# P-MT3620RDB-1-6_PIO.net
KiCad netlist of a schematic drawn in Altium Designer
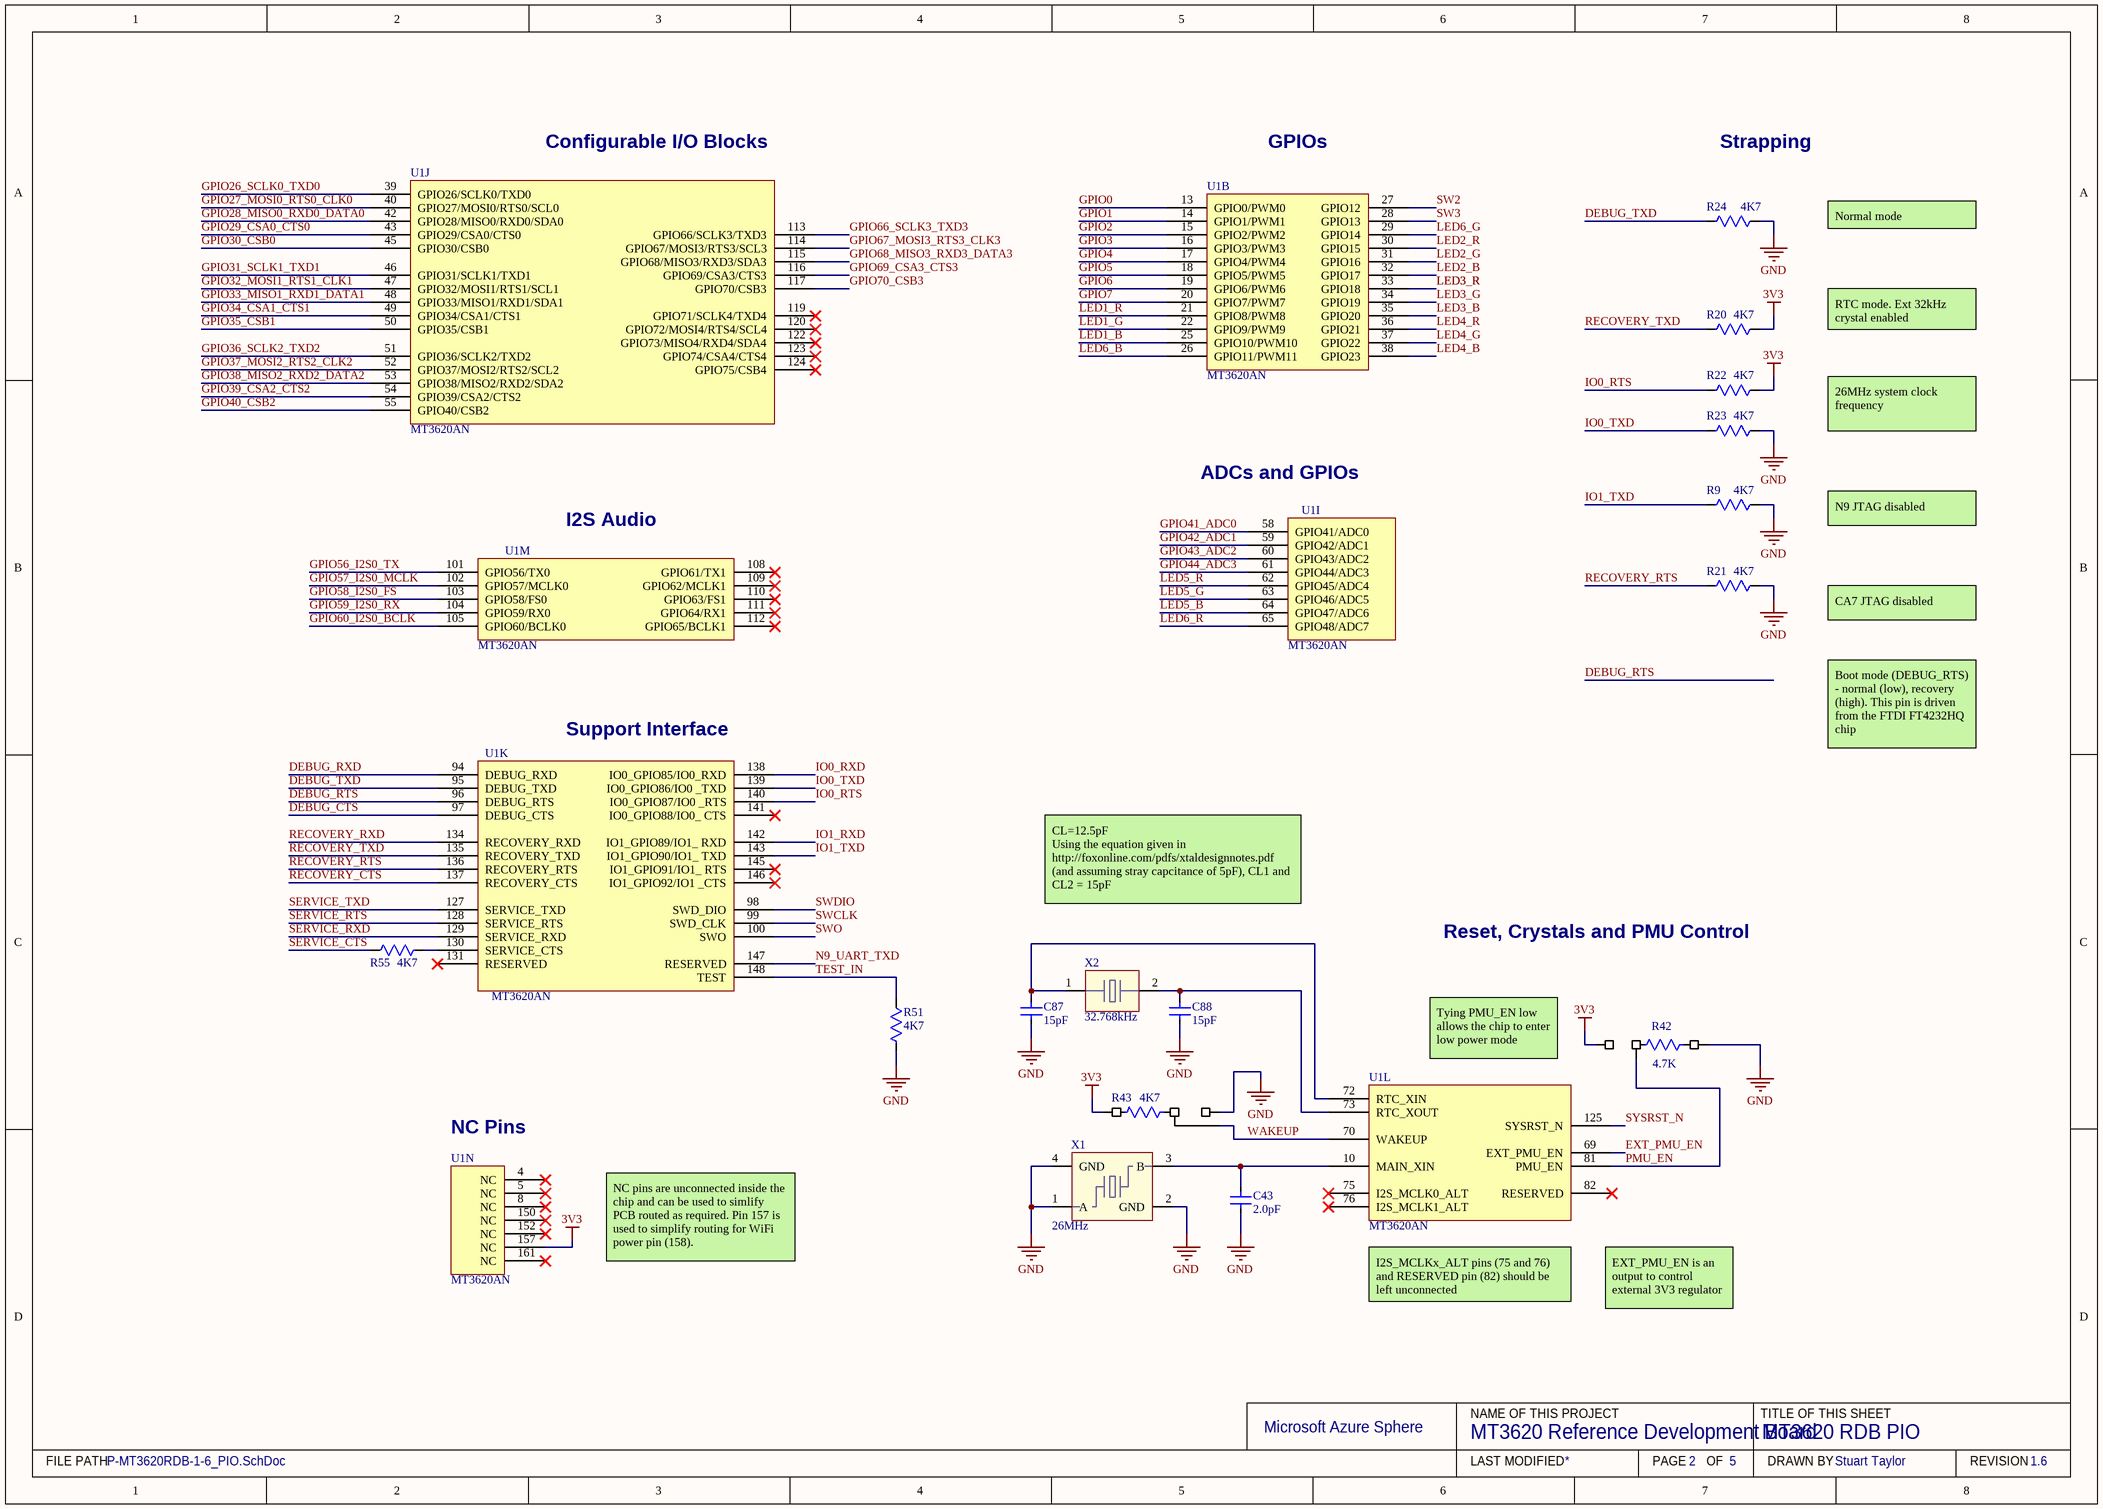
[diagram p0: P-MT3620RDB-1-6_PIO.SchDoc]

(export (version "E")
  (design (tool "Eeschema 10.0.6"))
  (components
    (comp (ref "C43")
      (value "2.0pF")
      (footprint "CAPC1005-EIA0402 0.55MM MED")
      (description "CAP CER 2PF 50V NP0 0402")
      (fields
        (field (name "MANUFACTURER") "TDK Corporation")
        (field (name "MANUFACTURER PART NUMBER") "C1005C0G1H020C050BA")
        (field (name "CAPACITANCE") "2.0pF")
      )
      (libsource (lib "TDK_Capacitor_C_0402") (part "2.0pF 0402 C0G, NP0 50V"))
    )
    (comp (ref "C87")
      (value "15pF")
      (footprint "CAPC1005-EIA0402 0.55MM MED")
      (description "CAP CER 15PF 50V 5% NP0 0402")
      (fields
        (field (name "MANUFACTURER") "TDK Corporation")
        (field (name "MANUFACTURER PART NUMBER") "C1005C0G1H150J050BA")
        (field (name "CAPACITANCE") "15pF")
      )
      (libsource (lib "TDK_Capacitor_C_0402") (part "15pF 0402 C0G, NP0 50V"))
    )
    (comp (ref "C88")
      (value "15pF")
      (footprint "CAPC1005-EIA0402 0.55MM MED")
      (description "CAP CER 15PF 50V 5% NP0 0402")
      (fields
        (field (name "MANUFACTURER") "TDK Corporation")
        (field (name "MANUFACTURER PART NUMBER") "C1005C0G1H150J050BA")
        (field (name "CAPACITANCE") "15pF")
      )
      (libsource (lib "TDK_Capacitor_C_0402") (part "15pF 0402 C0G, NP0 50V"))
    )
    (comp (ref "R9")
      (value "4K7")
      (footprint "RES 0402 MEDIUM DENSITY")
      (description "RES 4.7K OHM 1/10W 1% 0402 SMD")
      (fields
        (field (name "MANUFACTURER") "Panasonic Electronic Components")
        (field (name "MANUFACTURER PART NUMBER") "ERJ-2RKF4701X")
        (field (name "RESISTANCE (OHMS)") "4K7")
      )
      (libsource (lib "Panasonic_Resistor_ERJ2R") (part "4.7K"))
    )
    (comp (ref "R20")
      (value "4K7")
      (footprint "RES 0402 MEDIUM DENSITY")
      (description "RES 4.7K OHM 1/10W 1% 0402 SMD")
      (fields
        (field (name "MANUFACTURER") "Panasonic Electronic Components")
        (field (name "MANUFACTURER PART NUMBER") "ERJ-2RKF4701X")
        (field (name "RESISTANCE (OHMS)") "4K7")
      )
      (libsource (lib "Panasonic_Resistor_ERJ2R") (part "4.7K"))
    )
    (comp (ref "R21")
      (value "4K7")
      (footprint "RES 0402 MEDIUM DENSITY")
      (description "RES 4.7K OHM 1/10W 1% 0402 SMD")
      (fields
        (field (name "MANUFACTURER") "Panasonic Electronic Components")
        (field (name "MANUFACTURER PART NUMBER") "ERJ-2RKF4701X")
        (field (name "RESISTANCE (OHMS)") "4K7")
      )
      (libsource (lib "Panasonic_Resistor_ERJ2R") (part "4.7K"))
    )
    (comp (ref "R22")
      (value "4K7")
      (footprint "RES 0402 MEDIUM DENSITY")
      (description "RES 4.7K OHM 1/10W 1% 0402 SMD")
      (fields
        (field (name "MANUFACTURER") "Panasonic Electronic Components")
        (field (name "MANUFACTURER PART NUMBER") "ERJ-2RKF4701X")
        (field (name "RESISTANCE (OHMS)") "4K7")
      )
      (libsource (lib "Panasonic_Resistor_ERJ2R") (part "4.7K"))
    )
    (comp (ref "R23")
      (value "4K7")
      (footprint "RES 0402 MEDIUM DENSITY")
      (description "RES 4.7K OHM 1/10W 1% 0402 SMD")
      (fields
        (field (name "MANUFACTURER") "Panasonic Electronic Components")
        (field (name "MANUFACTURER PART NUMBER") "ERJ-2RKF4701X")
        (field (name "RESISTANCE (OHMS)") "4K7")
      )
      (libsource (lib "Panasonic_Resistor_ERJ2R") (part "4.7K"))
    )
    (comp (ref "R24")
      (value "4K7")
      (footprint "RES 0402 MEDIUM DENSITY")
      (description "RES 4.7K OHM 1/10W 1% 0402 SMD")
      (fields
        (field (name "MANUFACTURER") "Panasonic Electronic Components")
        (field (name "MANUFACTURER PART NUMBER") "ERJ-2RKF4701X")
        (field (name "RESISTANCE (OHMS)") "4K7")
      )
      (libsource (lib "Panasonic_Resistor_ERJ2R") (part "4.7K"))
    )
    (comp (ref "R42")
      (value "4.7K")
      (footprint "THREE-WAY-0402-NO-SHORT-RIGHT")
      (description "RES SMD 4.7K JUMPER 1/10W 0402")
      (fields
        (field (name "MANUFACTURER") "Panasonic Electronic Components")
        (field (name "MANUFACTURER PART NUMBER") "ERJ-2RKF4701X")
      )
      (libsource (lib "generic-res") (part "THREE-WAY-4K7-0402-NO-SHORT_RIGHT"))
    )
    (comp (ref "R43")
      (value "4K7")
      (footprint "THREE-WAY-0402-NO-SHORT")
      (description "RES SMD 4.7K JUMPER 1/10W 0402")
      (fields
        (field (name "MANUFACTURER") "Panasonic Electronic Components")
        (field (name "MANUFACTURER PART NUMBER") "ERJ-2RKF4701X")
      )
      (libsource (lib "generic-res") (part "THREE-WAY-4K7-0402-NO-SHORT"))
    )
    (comp (ref "R51")
      (value "4K7")
      (footprint "RES 0402 MEDIUM DENSITY")
      (description "RES 4.7K OHM 1/10W 1% 0402 SMD")
      (fields
        (field (name "MANUFACTURER") "Panasonic Electronic Components")
        (field (name "MANUFACTURER PART NUMBER") "ERJ-2RKF4701X")
        (field (name "RESISTANCE (OHMS)") "4K7")
      )
      (libsource (lib "Panasonic_Resistor_ERJ2R") (part "4.7K"))
    )
    (comp (ref "R55")
      (value "4K7")
      (footprint "RES 0402 MEDIUM DENSITY")
      (description "RES 4.7K OHM 1/10W 1% 0402 SMD")
      (fields
        (field (name "MANUFACTURER") "Panasonic Electronic Components")
        (field (name "MANUFACTURER PART NUMBER") "ERJ-2RKF4701X")
        (field (name "RESISTANCE (OHMS)") "4K7")
      )
      (libsource (lib "Panasonic_Resistor_ERJ2R") (part "4.7K"))
    )
    (comp (ref "U1")
      (value "MT3620AN")
      (footprint "MT3620_MaskSquaresVias50")
      (fields (field (name "MANUFACTURER") "MediaTek Inc."))
      (libsource (lib "Microsoft") (part "MT3620AN"))
    )
    (comp (ref "X1")
      (value "26MHz")
      (footprint "CT2520DB26000C0FZZA1")
      (description "26MHz crystal")
      (fields
        (field (name "MANUFACTURER") "Siward")
        (field (name "MANUFACTURER PART NUMBER") "XTL581100-M118-0804")
      )
      (libsource (lib "Siward") (part "XTL581100-M118-0804"))
    )
    (comp (ref "X2")
      (value "32.768kHz")
      (footprint "9HT10-32.768KDZF-T")
      (description "32.768kHz ±20ppm Crystal 12.5pF 70 kOhm -40°C ~ 85°C  Surface Mount 2-SMD")
      (fields
        (field (name "MANUFACTURER") "TXC")
        (field (name "MANUFACTURER PART NUMBER") "9HT10-32.768KDZF-T")
      )
      (libsource (lib "TXC") (part "9HT10-32.768KDZF-T"))
    )
  )
  (nets
    (net (code "1") (name "/DEBUG_CTS") (class "Default")
      (node (ref "U1") (pin "97") (pinfunction "DEBUG_CTS_97") (pintype "passive"))
    )
    (net (code "2") (name "/DEBUG_RTS") (class "Default")
      (node (ref "U1") (pin "96") (pinfunction "DEBUG_RTS_96") (pintype "passive"))
    )
    (net (code "3") (name "/DEBUG_RXD") (class "Default")
      (node (ref "U1") (pin "94") (pinfunction "DEBUG_RXD_94") (pintype "passive"))
    )
    (net (code "4") (name "/DEBUG_TXD") (class "Default")
      (node (ref "R24") (pin "2") (pinfunction "2_2") (pintype "passive"))
      (node (ref "U1") (pin "95") (pinfunction "DEBUG_TXD_95") (pintype "passive"))
    )
    (net (code "5") (name "/EXT_PMU_EN") (class "Default")
      (node (ref "U1") (pin "69") (pinfunction "EXT_PMU_EN_69") (pintype "passive"))
    )
    (net (code "6") (name "/GPIO0") (class "Default")
      (node (ref "U1") (pin "13") (pinfunction "GPIO0/PWM0_13") (pintype "passive"))
    )
    (net (code "7") (name "/GPIO1") (class "Default")
      (node (ref "U1") (pin "14") (pinfunction "GPIO1/PWM1_14") (pintype "passive"))
    )
    (net (code "8") (name "/GPIO2") (class "Default")
      (node (ref "U1") (pin "15") (pinfunction "GPIO2/PWM2_15") (pintype "passive"))
    )
    (net (code "9") (name "/GPIO3") (class "Default")
      (node (ref "U1") (pin "16") (pinfunction "GPIO3/PWM3_16") (pintype "passive"))
    )
    (net (code "10") (name "/GPIO4") (class "Default")
      (node (ref "U1") (pin "17") (pinfunction "GPIO4/PWM4_17") (pintype "passive"))
    )
    (net (code "11") (name "/GPIO5") (class "Default")
      (node (ref "U1") (pin "18") (pinfunction "GPIO5/PWM5_18") (pintype "passive"))
    )
    (net (code "12") (name "/GPIO6") (class "Default")
      (node (ref "U1") (pin "19") (pinfunction "GPIO6/PWM6_19") (pintype "passive"))
    )
    (net (code "13") (name "/GPIO7") (class "Default")
      (node (ref "U1") (pin "20") (pinfunction "GPIO7/PWM7_20") (pintype "passive"))
    )
    (net (code "14") (name "/GPIO26_SCLK0_TXD0") (class "Default")
      (node (ref "U1") (pin "39") (pinfunction "GPIO26/SCLK0/TXD0_39") (pintype "passive"))
    )
    (net (code "15") (name "/GPIO27_MOSI0_RTS0_CLK0") (class "Default")
      (node (ref "U1") (pin "40") (pinfunction "GPIO27/MOSI0/RTS0/SCL0_40") (pintype "passive"))
    )
    (net (code "16") (name "/GPIO28_MISO0_RXD0_DATA0") (class "Default")
      (node (ref "U1") (pin "42") (pinfunction "GPIO28/MISO0/RXD0/SDA0_42") (pintype "passive"))
    )
    (net (code "17") (name "/GPIO29_CSA0_CTS0") (class "Default")
      (node (ref "U1") (pin "43") (pinfunction "GPIO29/CSA0/CTS0_43") (pintype "passive"))
    )
    (net (code "18") (name "/GPIO30_CSB0") (class "Default")
      (node (ref "U1") (pin "45") (pinfunction "GPIO30/CSB0_45") (pintype "passive"))
    )
    (net (code "19") (name "/GPIO31_SCLK1_TXD1") (class "Default")
      (node (ref "U1") (pin "46") (pinfunction "GPIO31/SCLK1/TXD1_46") (pintype "passive"))
    )
    (net (code "20") (name "/GPIO32_MOSI1_RTS1_CLK1") (class "Default")
      (node (ref "U1") (pin "47") (pinfunction "GPIO32/MOSI1/RTS1/SCL1_47") (pintype "passive"))
    )
    (net (code "21") (name "/GPIO33_MISO1_RXD1_DATA1") (class "Default")
      (node (ref "U1") (pin "48") (pinfunction "GPIO33/MISO1/RXD1/SDA1_48") (pintype "passive"))
    )
    (net (code "22") (name "/GPIO34_CSA1_CTS1") (class "Default")
      (node (ref "U1") (pin "49") (pinfunction "GPIO34/CSA1/CTS1_49") (pintype "passive"))
    )
    (net (code "23") (name "/GPIO35_CSB1") (class "Default")
      (node (ref "U1") (pin "50") (pinfunction "GPIO35/CSB1_50") (pintype "passive"))
    )
    (net (code "24") (name "/GPIO36_SCLK2_TXD2") (class "Default")
      (node (ref "U1") (pin "51") (pinfunction "GPIO36/SCLK2/TXD2_51") (pintype "passive"))
    )
    (net (code "25") (name "/GPIO37_MOSI2_RTS2_CLK2") (class "Default")
      (node (ref "U1") (pin "52") (pinfunction "GPIO37/MOSI2/RTS2/SCL2_52") (pintype "passive"))
    )
    (net (code "26") (name "/GPIO38_MISO2_RXD2_DATA2") (class "Default")
      (node (ref "U1") (pin "53") (pinfunction "GPIO38/MISO2/RXD2/SDA2_53") (pintype "passive"))
    )
    (net (code "27") (name "/GPIO39_CSA2_CTS2") (class "Default")
      (node (ref "U1") (pin "54") (pinfunction "GPIO39/CSA2/CTS2_54") (pintype "passive"))
    )
    (net (code "28") (name "/GPIO40_CSB2") (class "Default")
      (node (ref "U1") (pin "55") (pinfunction "GPIO40/CSB2_55") (pintype "passive"))
    )
    (net (code "29") (name "/GPIO41_ADC0") (class "Default")
      (node (ref "U1") (pin "58") (pinfunction "GPIO41/ADC0_58") (pintype "passive"))
    )
    (net (code "30") (name "/GPIO42_ADC1") (class "Default")
      (node (ref "U1") (pin "59") (pinfunction "GPIO42/ADC1_59") (pintype "passive"))
    )
    (net (code "31") (name "/GPIO43_ADC2") (class "Default")
      (node (ref "U1") (pin "60") (pinfunction "GPIO43/ADC2_60") (pintype "passive"))
    )
    (net (code "32") (name "/GPIO44_ADC3") (class "Default")
      (node (ref "U1") (pin "61") (pinfunction "GPIO44/ADC3_61") (pintype "passive"))
    )
    (net (code "33") (name "/GPIO56_I2S0_TX") (class "Default")
      (node (ref "U1") (pin "101") (pinfunction "GPIO56/TX0_101") (pintype "passive"))
    )
    (net (code "34") (name "/GPIO57_I2S0_MCLK") (class "Default")
      (node (ref "U1") (pin "102") (pinfunction "GPIO57/MCLK0_102") (pintype "passive"))
    )
    (net (code "35") (name "/GPIO58_I2S0_FS") (class "Default")
      (node (ref "U1") (pin "103") (pinfunction "GPIO58/FS0_103") (pintype "passive"))
    )
    (net (code "36") (name "/GPIO59_I2S0_RX") (class "Default")
      (node (ref "U1") (pin "104") (pinfunction "GPIO59/RX0_104") (pintype "passive"))
    )
    (net (code "37") (name "/GPIO60_I2S0_BCLK") (class "Default")
      (node (ref "U1") (pin "105") (pinfunction "GPIO60/BCLK0_105") (pintype "passive"))
    )
    (net (code "38") (name "/GPIO66_SCLK3_TXD3") (class "Default")
      (node (ref "U1") (pin "113") (pinfunction "GPIO66/SCLK3/TXD3_113") (pintype "passive"))
    )
    (net (code "39") (name "/GPIO67_MOSI3_RTS3_CLK3") (class "Default")
      (node (ref "U1") (pin "114") (pinfunction "GPIO67/MOSI3/RTS3/SCL3_114") (pintype "passive"))
    )
    (net (code "40") (name "/GPIO68_MISO3_RXD3_DATA3") (class "Default")
      (node (ref "U1") (pin "115") (pinfunction "GPIO68/MISO3/RXD3/SDA3_115") (pintype "passive"))
    )
    (net (code "41") (name "/GPIO69_CSA3_CTS3") (class "Default")
      (node (ref "U1") (pin "116") (pinfunction "GPIO69/CSA3/CTS3_116") (pintype "passive"))
    )
    (net (code "42") (name "/GPIO70_CSB3") (class "Default")
      (node (ref "U1") (pin "117") (pinfunction "GPIO70/CSB3_117") (pintype "passive"))
    )
    (net (code "43") (name "/IO0_RTS") (class "Default")
      (node (ref "R22") (pin "2") (pinfunction "2_2") (pintype "passive"))
      (node (ref "U1") (pin "140") (pinfunction "IO0_GPIO87/IO0__RTS_140") (pintype "passive"))
    )
    (net (code "44") (name "/IO0_RXD") (class "Default")
      (node (ref "U1") (pin "138") (pinfunction "IO0_GPIO85/IO0_RXD_138") (pintype "passive"))
    )
    (net (code "45") (name "/IO0_TXD") (class "Default")
      (node (ref "R23") (pin "2") (pinfunction "2_2") (pintype "passive"))
      (node (ref "U1") (pin "139") (pinfunction "IO0_GPIO86/IO0__TXD_139") (pintype "passive"))
    )
    (net (code "46") (name "/IO1_RXD") (class "Default")
      (node (ref "U1") (pin "142") (pinfunction "IO1_GPIO89/IO1__RXD_142") (pintype "passive"))
    )
    (net (code "47") (name "/IO1_TXD") (class "Default")
      (node (ref "R9") (pin "2") (pinfunction "2_2") (pintype "passive"))
      (node (ref "U1") (pin "143") (pinfunction "IO1_GPIO90/IO1__TXD_143") (pintype "passive"))
    )
    (net (code "48") (name "/LED1_B") (class "Default")
      (node (ref "U1") (pin "25") (pinfunction "GPIO10/PWM10_25") (pintype "passive"))
    )
    (net (code "49") (name "/LED1_G") (class "Default")
      (node (ref "U1") (pin "22") (pinfunction "GPIO9/PWM9_22") (pintype "passive"))
    )
    (net (code "50") (name "/LED1_R") (class "Default")
      (node (ref "U1") (pin "21") (pinfunction "GPIO8/PWM8_21") (pintype "passive"))
    )
    (net (code "51") (name "/LED2_B") (class "Default")
      (node (ref "U1") (pin "32") (pinfunction "GPIO17_32") (pintype "passive"))
    )
    (net (code "52") (name "/LED2_G") (class "Default")
      (node (ref "U1") (pin "31") (pinfunction "GPIO16_31") (pintype "passive"))
    )
    (net (code "53") (name "/LED2_R") (class "Default")
      (node (ref "U1") (pin "30") (pinfunction "GPIO15_30") (pintype "passive"))
    )
    (net (code "54") (name "/LED3_B") (class "Default")
      (node (ref "U1") (pin "35") (pinfunction "GPIO20_35") (pintype "passive"))
    )
    (net (code "55") (name "/LED3_G") (class "Default")
      (node (ref "U1") (pin "34") (pinfunction "GPIO19_34") (pintype "passive"))
    )
    (net (code "56") (name "/LED3_R") (class "Default")
      (node (ref "U1") (pin "33") (pinfunction "GPIO18_33") (pintype "passive"))
    )
    (net (code "57") (name "/LED4_B") (class "Default")
      (node (ref "U1") (pin "38") (pinfunction "GPIO23_38") (pintype "passive"))
    )
    (net (code "58") (name "/LED4_G") (class "Default")
      (node (ref "U1") (pin "37") (pinfunction "GPIO22_37") (pintype "passive"))
    )
    (net (code "59") (name "/LED4_R") (class "Default")
      (node (ref "U1") (pin "36") (pinfunction "GPIO21_36") (pintype "passive"))
    )
    (net (code "60") (name "/LED5_B") (class "Default")
      (node (ref "U1") (pin "64") (pinfunction "GPIO47/ADC6_64") (pintype "passive"))
    )
    (net (code "61") (name "/LED5_G") (class "Default")
      (node (ref "U1") (pin "63") (pinfunction "GPIO46/ADC5_63") (pintype "passive"))
    )
    (net (code "62") (name "/LED5_R") (class "Default")
      (node (ref "U1") (pin "62") (pinfunction "GPIO45/ADC4_62") (pintype "passive"))
    )
    (net (code "63") (name "/LED6_B") (class "Default")
      (node (ref "U1") (pin "26") (pinfunction "GPIO11/PWM11_26") (pintype "passive"))
    )
    (net (code "64") (name "/LED6_G") (class "Default")
      (node (ref "U1") (pin "29") (pinfunction "GPIO14_29") (pintype "passive"))
    )
    (net (code "65") (name "/LED6_R") (class "Default")
      (node (ref "U1") (pin "65") (pinfunction "GPIO48/ADC7_65") (pintype "passive"))
    )
    (net (code "66") (name "/N9_UART_TXD") (class "Default")
      (node (ref "U1") (pin "147") (pinfunction "RESERVED_147") (pintype "passive"))
    )
    (net (code "67") (name "/PMU_EN") (class "Default")
      (node (ref "R42") (pin "2") (pinfunction "2_2") (pintype "passive"))
      (node (ref "U1") (pin "81") (pinfunction "PMU_EN_81") (pintype "passive"))
    )
    (net (code "68") (name "/RECOVERY_CTS") (class "Default")
      (node (ref "U1") (pin "137") (pinfunction "RECOVERY_CTS_137") (pintype "passive"))
    )
    (net (code "69") (name "/RECOVERY_RTS") (class "Default")
      (node (ref "R21") (pin "2") (pinfunction "2_2") (pintype "passive"))
      (node (ref "U1") (pin "136") (pinfunction "RECOVERY_RTS_136") (pintype "passive"))
    )
    (net (code "70") (name "/RECOVERY_RXD") (class "Default")
      (node (ref "U1") (pin "134") (pinfunction "RECOVERY_RXD_134") (pintype "passive"))
    )
    (net (code "71") (name "/RECOVERY_TXD") (class "Default")
      (node (ref "R20") (pin "2") (pinfunction "2_2") (pintype "passive"))
      (node (ref "U1") (pin "135") (pinfunction "RECOVERY_TXD_135") (pintype "passive"))
    )
    (net (code "72") (name "/SERVICE_CTS") (class "Default")
      (node (ref "R55") (pin "1") (pinfunction "1_1") (pintype "passive"))
    )
    (net (code "73") (name "/SERVICE_RTS") (class "Default")
      (node (ref "U1") (pin "128") (pinfunction "SERVICE_RTS_128") (pintype "passive"))
    )
    (net (code "74") (name "/SERVICE_RXD") (class "Default")
      (node (ref "U1") (pin "129") (pinfunction "SERVICE_RXD_129") (pintype "passive"))
    )
    (net (code "75") (name "/SERVICE_TXD") (class "Default")
      (node (ref "U1") (pin "127") (pinfunction "SERVICE_TXD_127") (pintype "passive"))
    )
    (net (code "76") (name "/SW2") (class "Default")
      (node (ref "U1") (pin "27") (pinfunction "GPIO12_27") (pintype "passive"))
    )
    (net (code "77") (name "/SW3") (class "Default")
      (node (ref "U1") (pin "28") (pinfunction "GPIO13_28") (pintype "passive"))
    )
    (net (code "78") (name "/SWCLK") (class "Default")
      (node (ref "U1") (pin "99") (pinfunction "SWD_CLK_99") (pintype "passive"))
    )
    (net (code "79") (name "/SWDIO") (class "Default")
      (node (ref "U1") (pin "98") (pinfunction "SWD_DIO_98") (pintype "passive"))
    )
    (net (code "80") (name "/SWO") (class "Default")
      (node (ref "U1") (pin "100") (pinfunction "SWO_100") (pintype "passive"))
    )
    (net (code "81") (name "/SYSRST_N") (class "Default")
      (node (ref "U1") (pin "125") (pinfunction "SYSRST_N_125") (pintype "passive"))
    )
    (net (code "82") (name "/TEST_IN") (class "Default")
      (node (ref "R51") (pin "1") (pinfunction "1_1") (pintype "passive"))
      (node (ref "U1") (pin "148") (pinfunction "TEST_148") (pintype "passive"))
    )
    (net (code "83") (name "/WAKEUP") (class "Default")
      (node (ref "R43") (pin "2") (pinfunction "2_2") (pintype "passive"))
      (node (ref "U1") (pin "70") (pinfunction "WAKEUP_70") (pintype "passive"))
    )
    (net (code "84") (name "3V3") (class "Default")
      (node (ref "R20") (pin "1") (pinfunction "1_1") (pintype "passive"))
      (node (ref "R22") (pin "1") (pinfunction "1_1") (pintype "passive"))
      (node (ref "R42") (pin "1") (pinfunction "1_1") (pintype "passive"))
      (node (ref "R43") (pin "1") (pinfunction "1_1") (pintype "passive"))
      (node (ref "U1") (pin "157") (pinfunction "NC_157") (pintype "passive"))
    )
    (net (code "85") (name "GND") (class "Default")
      (node (ref "C43") (pin "1") (pinfunction "1_1") (pintype "passive"))
      (node (ref "C87") (pin "1") (pinfunction "1_1") (pintype "passive"))
      (node (ref "C88") (pin "1") (pinfunction "1_1") (pintype "passive"))
      (node (ref "R21") (pin "1") (pinfunction "1_1") (pintype "passive"))
      (node (ref "R23") (pin "1") (pinfunction "1_1") (pintype "passive"))
      (node (ref "R24") (pin "1") (pinfunction "1_1") (pintype "passive"))
      (node (ref "R42") (pin "3") (pinfunction "3_3") (pintype "passive"))
      (node (ref "R43") (pin "3") (pinfunction "3_3") (pintype "passive"))
      (node (ref "R51") (pin "2") (pinfunction "2_2") (pintype "passive"))
      (node (ref "R9") (pin "1") (pinfunction "1_1") (pintype "passive"))
      (node (ref "X1") (pin "1") (pinfunction "A_1") (pintype "passive"))
      (node (ref "X1") (pin "2") (pinfunction "GND_2") (pintype "passive"))
      (node (ref "X1") (pin "4") (pinfunction "GND_4") (pintype "passive"))
    )
    (net (code "86") (name "Net-(U1K-SERVICE_CTS)") (class "Default")
      (node (ref "R55") (pin "2") (pinfunction "2_2") (pintype "passive"))
      (node (ref "U1") (pin "130") (pinfunction "SERVICE_CTS_130") (pintype "passive"))
    )
    (net (code "87") (name "Net-(U1L-MAIN_XIN)") (class "Default")
      (node (ref "C43") (pin "2") (pinfunction "2_2") (pintype "passive"))
      (node (ref "U1") (pin "10") (pinfunction "MAIN_XIN_10") (pintype "passive"))
      (node (ref "X1") (pin "3") (pinfunction "B_3") (pintype "passive"))
    )
    (net (code "88") (name "Net-(U1L-RTC_XIN)") (class "Default")
      (node (ref "C87") (pin "2") (pinfunction "2_2") (pintype "passive"))
      (node (ref "U1") (pin "72") (pinfunction "RTC_XIN_72") (pintype "passive"))
      (node (ref "X2") (pin "1") (pinfunction "1_1") (pintype "passive"))
    )
    (net (code "89") (name "Net-(U1L-RTC_XOUT)") (class "Default")
      (node (ref "C88") (pin "2") (pinfunction "2_2") (pintype "passive"))
      (node (ref "U1") (pin "73") (pinfunction "RTC_XOUT_73") (pintype "passive"))
      (node (ref "X2") (pin "2") (pinfunction "2_2") (pintype "passive"))
    )
    (net (code "90") (name "unconnected-(U1J-GPIO71{slash}SCLK4{slash}TXD4-Pad119)") (class "Default")
      (node (ref "U1") (pin "119") (pinfunction "GPIO71/SCLK4/TXD4_119") (pintype "passive+no_connect"))
    )
    (net (code "91") (name "unconnected-(U1J-GPIO72{slash}MOSI4{slash}RTS4{slash}SCL4-Pad120)") (class "Default")
      (node (ref "U1") (pin "120") (pinfunction "GPIO72/MOSI4/RTS4/SCL4_120") (pintype "passive+no_connect"))
    )
    (net (code "92") (name "unconnected-(U1J-GPIO73{slash}MISO4{slash}RXD4{slash}SDA4-Pad122)") (class "Default")
      (node (ref "U1") (pin "122") (pinfunction "GPIO73/MISO4/RXD4/SDA4_122") (pintype "passive+no_connect"))
    )
    (net (code "93") (name "unconnected-(U1J-GPIO74{slash}CSA4{slash}CTS4-Pad123)") (class "Default")
      (node (ref "U1") (pin "123") (pinfunction "GPIO74/CSA4/CTS4_123") (pintype "passive+no_connect"))
    )
    (net (code "94") (name "unconnected-(U1J-GPIO75{slash}CSB4-Pad124)") (class "Default")
      (node (ref "U1") (pin "124") (pinfunction "GPIO75/CSB4_124") (pintype "passive+no_connect"))
    )
    (net (code "95") (name "unconnected-(U1K-IO0_GPIO88{slash}IO0__CTS-Pad141)") (class "Default")
      (node (ref "U1") (pin "141") (pinfunction "IO0_GPIO88/IO0__CTS_141") (pintype "passive+no_connect"))
    )
    (net (code "96") (name "unconnected-(U1K-IO1_GPIO91{slash}IO1__RTS-Pad145)") (class "Default")
      (node (ref "U1") (pin "145") (pinfunction "IO1_GPIO91/IO1__RTS_145") (pintype "passive+no_connect"))
    )
    (net (code "97") (name "unconnected-(U1K-IO1_GPIO92{slash}IO1__CTS-Pad146)") (class "Default")
      (node (ref "U1") (pin "146") (pinfunction "IO1_GPIO92/IO1__CTS_146") (pintype "passive+no_connect"))
    )
    (net (code "98") (name "unconnected-(U1K-RESERVED-Pad131)") (class "Default")
      (node (ref "U1") (pin "131") (pinfunction "RESERVED_131") (pintype "passive+no_connect"))
    )
    (net (code "99") (name "unconnected-(U1L-I2S_MCLK0_ALT-Pad75)") (class "Default")
      (node (ref "U1") (pin "75") (pinfunction "I2S_MCLK0_ALT_75") (pintype "passive+no_connect"))
    )
    (net (code "100") (name "unconnected-(U1L-I2S_MCLK1_ALT-Pad76)") (class "Default")
      (node (ref "U1") (pin "76") (pinfunction "I2S_MCLK1_ALT_76") (pintype "passive+no_connect"))
    )
    (net (code "101") (name "unconnected-(U1L-RESERVED-Pad82)") (class "Default")
      (node (ref "U1") (pin "82") (pinfunction "RESERVED_82") (pintype "passive+no_connect"))
    )
    (net (code "102") (name "unconnected-(U1M-GPIO61{slash}TX1-Pad108)") (class "Default")
      (node (ref "U1") (pin "108") (pinfunction "GPIO61/TX1_108") (pintype "passive+no_connect"))
    )
    (net (code "103") (name "unconnected-(U1M-GPIO62{slash}MCLK1-Pad109)") (class "Default")
      (node (ref "U1") (pin "109") (pinfunction "GPIO62/MCLK1_109") (pintype "passive+no_connect"))
    )
    (net (code "104") (name "unconnected-(U1M-GPIO63{slash}FS1-Pad110)") (class "Default")
      (node (ref "U1") (pin "110") (pinfunction "GPIO63/FS1_110") (pintype "passive+no_connect"))
    )
    (net (code "105") (name "unconnected-(U1M-GPIO64{slash}RX1-Pad111)") (class "Default")
      (node (ref "U1") (pin "111") (pinfunction "GPIO64/RX1_111") (pintype "passive+no_connect"))
    )
    (net (code "106") (name "unconnected-(U1M-GPIO65{slash}BCLK1-Pad112)") (class "Default")
      (node (ref "U1") (pin "112") (pinfunction "GPIO65/BCLK1_112") (pintype "passive+no_connect"))
    )
    (net (code "107") (name "unconnected-(U1N-NC-Pad4)") (class "Default")
      (node (ref "U1") (pin "4") (pinfunction "NC_4") (pintype "passive+no_connect"))
    )
    (net (code "108") (name "unconnected-(U1N-NC-Pad5)") (class "Default")
      (node (ref "U1") (pin "5") (pinfunction "NC_5") (pintype "passive+no_connect"))
    )
    (net (code "109") (name "unconnected-(U1N-NC-Pad8)") (class "Default")
      (node (ref "U1") (pin "8") (pinfunction "NC_8") (pintype "passive+no_connect"))
    )
    (net (code "110") (name "unconnected-(U1N-NC-Pad150)") (class "Default")
      (node (ref "U1") (pin "150") (pinfunction "NC_150") (pintype "passive+no_connect"))
    )
    (net (code "111") (name "unconnected-(U1N-NC-Pad152)") (class "Default")
      (node (ref "U1") (pin "152") (pinfunction "NC_152") (pintype "passive+no_connect"))
    )
    (net (code "112") (name "unconnected-(U1N-NC-Pad161)") (class "Default")
      (node (ref "U1") (pin "161") (pinfunction "NC_161") (pintype "passive+no_connect"))
    )
  )
)
